# Schematic.net
KiCad netlist of a schematic drawn in Altium Designer
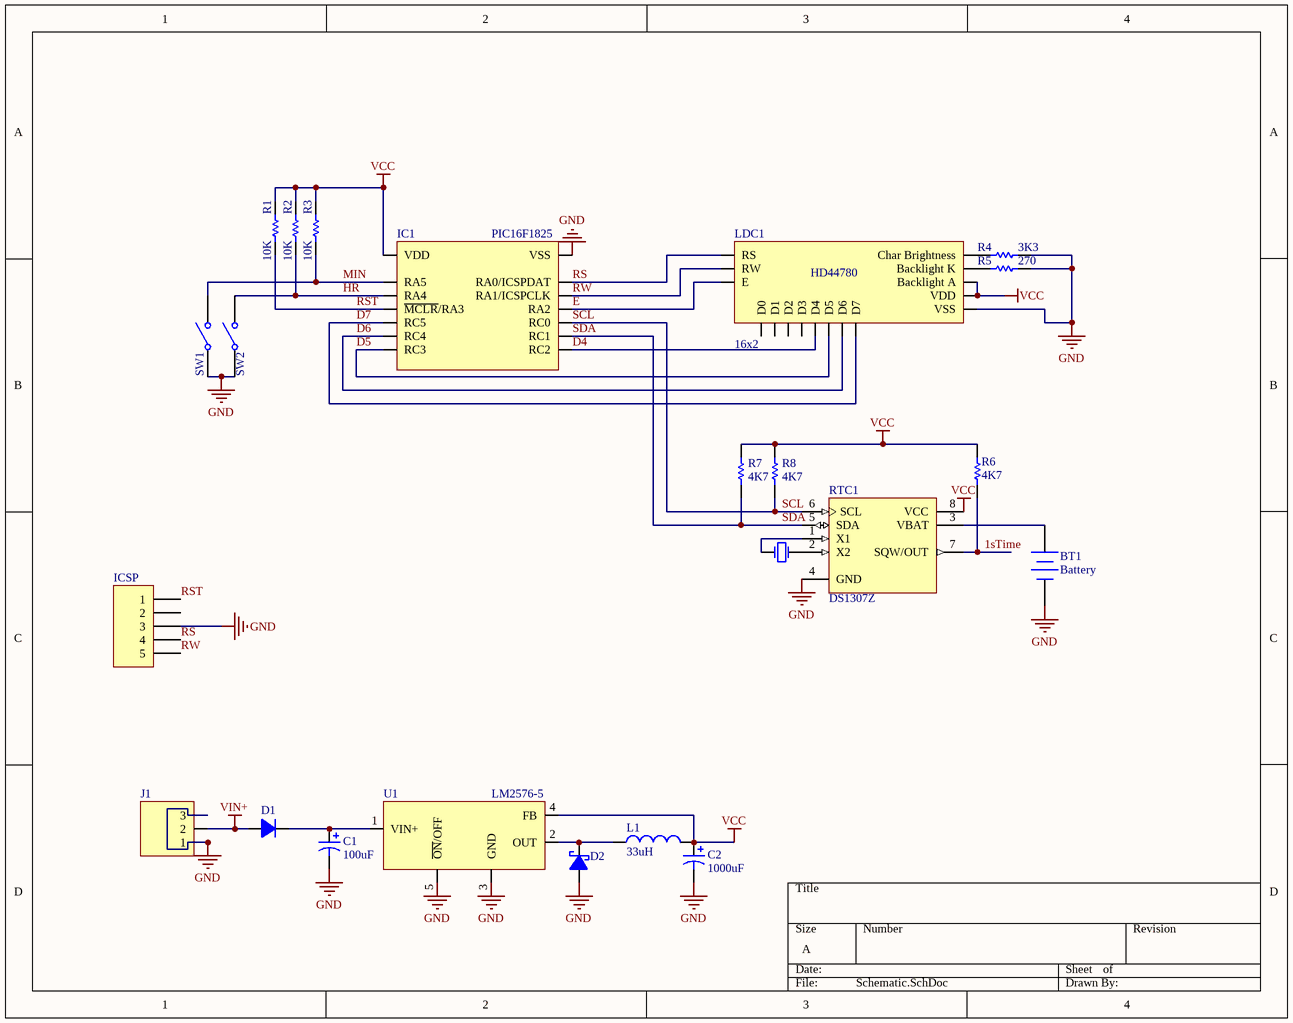
[diagram p0: Schematic.SchDoc]

(export (version "E")
  (design (tool "Eeschema 10.0.6"))
  (components
    (comp (ref "BT1")
      (value "Battery")
      (footprint "Moji Footprintovi:CR2032 Holder")
      (description "Multicell Battery")
      (fields (field (name "PUBLISHER") "Altium Limited"))
      (libsource (lib "Moji Schematici") (part "Battery"))
    )
    (comp (ref "C1")
      (value "100uF")
      (footprint "Electrolytic Cap2")
      (description "Polarized Capacitor (Axial)")
      (fields (field (name "Comment") "100uF / 50V") (field (name "PUBLISHER") "Altium Limited"))
      (libsource (lib "Moji Schematici") (part "Cap Electrolytic"))
    )
    (comp (ref "C2")
      (value "1000uF")
      (footprint "Electrolytic Cap2")
      (description "Polarized Capacitor (Axial)")
      (fields (field (name "Comment") "1000uF / 16V") (field (name "PUBLISHER") "Altium Limited"))
      (libsource (lib "Moji Schematici") (part "Cap Electrolytic"))
    )
    (comp (ref "D1")
      (value "Diode")
      (footprint "Moji Footprintovi:Axial 0.3 - Polarized")
      (fields (field (name "PUBLISHER") "Altium Limited"))
      (libsource (lib "Moji Schematici") (part "Diode"))
    )
    (comp (ref "D2")
      (value "1N5822")
      (footprint "Moji Footprintovi:Axial 0.3 - Polarized")
      (fields (field (name "PUBLISHER") "Altium Limited"))
      (libsource (lib "Moji Schematici") (part "Diode Schotky"))
    )
    (comp (ref "IC1")
      (value "PIC16F1825")
      (footprint "Moji Footprintovi:DIP14-300mil")
      (libsource (lib "Moji Schematici") (part "PIC16F1825"))
    )
    (comp (ref "ICSP")
      (value "Header 5")
      (footprint "HDR1X5")
      (description "Header, 5-Pin")
      (fields (field (name "PUBLISHER") "Altium Limited"))
      (libsource (lib "Miscellaneous Connectors") (part "Header 5"))
    )
    (comp (ref "J1")
      (value "Jack Mini Inline")
      (footprint "Jack Mini Inline")
      (libsource (lib "Moji Schematici") (part "Jack Mini Inline"))
    )
    (comp (ref "L1")
      (value "33uH")
      (footprint "Moji Footprintovi:CW8A")
      (description "Inductor")
      (fields (field (name "PUBLISHER") "Altium Limited"))
      (libsource (lib "Moji Schematici") (part "Inductor"))
    )
    (comp (ref "LDC1")
      (value "16x2")
      (footprint "Moji Footprintovi:HD44780")
      (description "HD44780 16x2 LCD Display")
      (libsource (lib "Moji Schematici") (part "HD44780"))
    )
    (comp (ref "R1")
      (value "10K")
      (footprint "Moji Footprintovi:0805")
      (description "Resistor")
      (fields (field (name "Comment") "Res") (field (name "PUBLISHER") "Altium Limited"))
      (libsource (lib "Moji Schematici") (part "Res"))
    )
    (comp (ref "R2")
      (value "10K")
      (footprint "Moji Footprintovi:0805")
      (description "Resistor")
      (fields (field (name "Comment") "Res") (field (name "PUBLISHER") "Altium Limited"))
      (libsource (lib "Moji Schematici") (part "Res"))
    )
    (comp (ref "R3")
      (value "10K")
      (footprint "Moji Footprintovi:0805")
      (description "Resistor")
      (fields (field (name "Comment") "Res") (field (name "PUBLISHER") "Altium Limited"))
      (libsource (lib "Moji Schematici") (part "Res"))
    )
    (comp (ref "R4")
      (value "3K3")
      (footprint "Moji Footprintovi:Axial 0.4")
      (description "Resistor")
      (fields (field (name "Comment") "Res") (field (name "PUBLISHER") "Altium Limited"))
      (libsource (lib "Moji Schematici") (part "Res"))
    )
    (comp (ref "R5")
      (value "270")
      (footprint "Moji Footprintovi:Axial 0.4")
      (description "Resistor")
      (fields (field (name "Comment") "Res") (field (name "PUBLISHER") "Altium Limited"))
      (libsource (lib "Moji Schematici") (part "Res"))
    )
    (comp (ref "R6")
      (value "4K7")
      (footprint "Moji Footprintovi:0805")
      (description "Resistor")
      (fields (field (name "Comment") "Res") (field (name "PUBLISHER") "Altium Limited"))
      (libsource (lib "Moji Schematici") (part "Res"))
    )
    (comp (ref "R7")
      (value "4K7")
      (footprint "Moji Footprintovi:0805")
      (description "Resistor")
      (fields (field (name "Comment") "Res") (field (name "PUBLISHER") "Altium Limited"))
      (libsource (lib "Moji Schematici") (part "Res"))
    )
    (comp (ref "R8")
      (value "4K7")
      (footprint "Moji Footprintovi:0805")
      (description "Resistor")
      (fields (field (name "Comment") "Res") (field (name "PUBLISHER") "Altium Limited"))
      (libsource (lib "Moji Schematici") (part "Res"))
    )
    (comp (ref "RTC1")
      (value "DS1307Z")
      (footprint "SOIC8N_N")
      (description "64 X 8 Serial Real-Time Clock")
      (fields (field (name "PUBLISHER") "Altium Limited"))
      (libsource (lib "Dallas Peripheral Real Time Clock") (part "DS1307Z"))
    )
    (comp (ref "SW1")
      (value "Switch")
      (footprint "SMD Switch 2pin")
      (libsource (lib "Moji Schematici") (part "Switch"))
    )
    (comp (ref "SW2")
      (value "Switch")
      (footprint "SMD Switch 2pin")
      (libsource (lib "Moji Schematici") (part "Switch"))
    )
    (comp (ref "U1")
      (value "LM2576-5")
      (footprint "Moji Footprintovi:TO263-5")
      (libsource (lib "Moji Schematici") (part "LM257-xx"))
    )
    (comp (ref "Y1")
      (value "XTAL")
      (footprint "Moji Footprintovi:XTAL-Watch")
      (description "Crystal Oscillator")
      (fields (field (name "PUBLISHER") "Altium Limited"))
      (libsource (lib "Moji Schematici") (part "XTAL"))
    )
  )
  (nets
    (net (code "1") (name "/1sTime") (class "Default")
      (node (ref "R6") (pin "2") (pinfunction "2_2") (pintype "passive"))
      (node (ref "RTC1") (pin "7") (pinfunction "SQW/OUT_7") (pintype "output"))
    )
    (net (code "2") (name "/D4") (class "Default")
      (node (ref "IC1") (pin "8") (pinfunction "RC2_8") (pintype "passive"))
      (node (ref "LDC1") (pin "D4") (pinfunction "D4_D4") (pintype "passive"))
    )
    (net (code "3") (name "/D5") (class "Default")
      (node (ref "IC1") (pin "7") (pinfunction "RC3_7") (pintype "passive"))
      (node (ref "LDC1") (pin "D5") (pinfunction "D5_D5") (pintype "passive"))
    )
    (net (code "4") (name "/D6") (class "Default")
      (node (ref "IC1") (pin "6") (pinfunction "RC4_6") (pintype "passive"))
      (node (ref "LDC1") (pin "D6") (pinfunction "D6_D6") (pintype "passive"))
    )
    (net (code "5") (name "/D7") (class "Default")
      (node (ref "IC1") (pin "5") (pinfunction "RC5_5") (pintype "passive"))
      (node (ref "LDC1") (pin "D7") (pinfunction "D7_D7") (pintype "passive"))
    )
    (net (code "6") (name "/E") (class "Default")
      (node (ref "IC1") (pin "11") (pinfunction "RA2_11") (pintype "passive"))
      (node (ref "LDC1") (pin "E") (pinfunction "E_E") (pintype "passive"))
    )
    (net (code "7") (name "/HR") (class "Default")
      (node (ref "IC1") (pin "3") (pinfunction "RA4_3") (pintype "passive"))
      (node (ref "R2") (pin "1") (pinfunction "1_1") (pintype "passive"))
      (node (ref "SW2") (pin "2") (pinfunction "COMMON2_2") (pintype "passive"))
    )
    (net (code "8") (name "/MIN") (class "Default")
      (node (ref "IC1") (pin "2") (pinfunction "RA5_2") (pintype "passive"))
      (node (ref "R3") (pin "1") (pinfunction "1_1") (pintype "passive"))
      (node (ref "SW1") (pin "2") (pinfunction "COMMON2_2") (pintype "passive"))
    )
    (net (code "9") (name "/RS") (class "Default")
      (node (ref "IC1") (pin "13") (pinfunction "RA0/ICSPDAT_13") (pintype "passive"))
      (node (ref "ICSP") (pin "4") (pinfunction "4_4") (pintype "passive"))
      (node (ref "LDC1") (pin "RS") (pinfunction "RS_RS") (pintype "passive"))
    )
    (net (code "10") (name "/RST") (class "Default")
      (node (ref "IC1") (pin "4") (pinfunction "~{MCLR}/RA3_4") (pintype "passive"))
      (node (ref "ICSP") (pin "1") (pinfunction "1_1") (pintype "passive"))
      (node (ref "R1") (pin "1") (pinfunction "1_1") (pintype "passive"))
    )
    (net (code "11") (name "/RW") (class "Default")
      (node (ref "IC1") (pin "12") (pinfunction "RA1/ICSPCLK_12") (pintype "passive"))
      (node (ref "ICSP") (pin "5") (pinfunction "5_5") (pintype "passive"))
      (node (ref "LDC1") (pin "RW") (pinfunction "RW_RW") (pintype "passive"))
    )
    (net (code "12") (name "/SCL") (class "Default")
      (node (ref "IC1") (pin "10") (pinfunction "RC0_10") (pintype "passive"))
      (node (ref "R8") (pin "1") (pinfunction "1_1") (pintype "passive"))
      (node (ref "RTC1") (pin "6") (pinfunction "SCL_6") (pintype "input"))
    )
    (net (code "13") (name "/SDA") (class "Default")
      (node (ref "IC1") (pin "9") (pinfunction "RC1_9") (pintype "passive"))
      (node (ref "R7") (pin "1") (pinfunction "1_1") (pintype "passive"))
      (node (ref "RTC1") (pin "5") (pinfunction "SDA_5") (pintype "bidirectional"))
    )
    (net (code "14") (name "GND") (class "Default")
      (node (ref "BT1") (pin "2") (pinfunction "-_2") (pintype "passive"))
      (node (ref "C1") (pin "2") (pinfunction "2_2") (pintype "passive"))
      (node (ref "C2") (pin "2") (pinfunction "2_2") (pintype "passive"))
      (node (ref "D2") (pin "A") (pinfunction "A_A") (pintype "passive"))
      (node (ref "IC1") (pin "14") (pinfunction "VSS_14") (pintype "passive"))
      (node (ref "ICSP") (pin "3") (pinfunction "3_3") (pintype "passive"))
      (node (ref "J1") (pin "1") (pinfunction "1_1") (pintype "passive"))
      (node (ref "J1") (pin "3") (pinfunction "3_3") (pintype "passive"))
      (node (ref "LDC1") (pin "VSS") (pinfunction "VSS_VSS") (pintype "passive"))
      (node (ref "R4") (pin "2") (pinfunction "2_2") (pintype "passive"))
      (node (ref "R5") (pin "1") (pinfunction "1_1") (pintype "passive"))
      (node (ref "RTC1") (pin "4") (pinfunction "GND_4") (pintype "power_in"))
      (node (ref "SW1") (pin "1") (pinfunction "COMMON1_1") (pintype "passive"))
      (node (ref "SW2") (pin "1") (pinfunction "COMMON1_1") (pintype "passive"))
      (node (ref "U1") (pin "3") (pinfunction "GND_3") (pintype "passive"))
      (node (ref "U1") (pin "5") (pinfunction "~{ON}/OFF_5") (pintype "passive"))
    )
    (net (code "15") (name "Net-(BT1-+)") (class "Default")
      (node (ref "BT1") (pin "1") (pinfunction "+_1") (pintype "passive"))
      (node (ref "RTC1") (pin "3") (pinfunction "VBAT_3") (pintype "power_in"))
    )
    (net (code "16") (name "Net-(LDC1-Backlight_K)") (class "Default")
      (node (ref "LDC1") (pin "K") (pinfunction "Backlight_K_K") (pintype "passive"))
      (node (ref "R5") (pin "2") (pinfunction "2_2") (pintype "passive"))
    )
    (net (code "17") (name "Net-(LDC1-Char_Brightness)") (class "Default")
      (node (ref "LDC1") (pin "BRTN") (pinfunction "Char_Brightness_BRTN") (pintype "passive"))
      (node (ref "R4") (pin "1") (pinfunction "1_1") (pintype "passive"))
    )
    (net (code "18") (name "Net-(RTC1-X1)") (class "Default")
      (node (ref "RTC1") (pin "1") (pinfunction "X1_1") (pintype "input"))
      (node (ref "Y1") (pin "1") (pinfunction "OSC1_1") (pintype "passive"))
    )
    (net (code "19") (name "Net-(RTC1-X2)") (class "Default")
      (node (ref "RTC1") (pin "2") (pinfunction "X2_2") (pintype "input"))
      (node (ref "Y1") (pin "2") (pinfunction "OSC2_2") (pintype "passive"))
    )
    (net (code "20") (name "Net-(U1-OUT)") (class "Default")
      (node (ref "D2") (pin "K") (pinfunction "K_K") (pintype "passive"))
      (node (ref "L1") (pin "1") (pinfunction "1_1") (pintype "passive"))
      (node (ref "U1") (pin "2") (pinfunction "OUT_2") (pintype "passive"))
    )
    (net (code "21") (name "Net-(U1-VIN+)") (class "Default")
      (node (ref "C1") (pin "1") (pinfunction "1_1") (pintype "passive"))
      (node (ref "D1") (pin "K") (pinfunction "K_K") (pintype "passive"))
      (node (ref "U1") (pin "1") (pinfunction "VIN+_1") (pintype "passive"))
    )
    (net (code "22") (name "VCC") (class "Default")
      (node (ref "C2") (pin "1") (pinfunction "1_1") (pintype "passive"))
      (node (ref "IC1") (pin "1") (pinfunction "VDD_1") (pintype "passive"))
      (node (ref "L1") (pin "2") (pinfunction "2_2") (pintype "passive"))
      (node (ref "LDC1") (pin "A") (pinfunction "Backlight_A_A") (pintype "passive"))
      (node (ref "LDC1") (pin "VDD") (pinfunction "VDD_VDD") (pintype "passive"))
      (node (ref "R1") (pin "2") (pinfunction "2_2") (pintype "passive"))
      (node (ref "R2") (pin "2") (pinfunction "2_2") (pintype "passive"))
      (node (ref "R3") (pin "2") (pinfunction "2_2") (pintype "passive"))
      (node (ref "R6") (pin "1") (pinfunction "1_1") (pintype "passive"))
      (node (ref "R7") (pin "2") (pinfunction "2_2") (pintype "passive"))
      (node (ref "R8") (pin "2") (pinfunction "2_2") (pintype "passive"))
      (node (ref "RTC1") (pin "8") (pinfunction "VCC_8") (pintype "power_in"))
      (node (ref "U1") (pin "4") (pinfunction "FB_4") (pintype "passive"))
    )
    (net (code "23") (name "VIN+") (class "Default")
      (node (ref "D1") (pin "A") (pinfunction "A_A") (pintype "passive"))
      (node (ref "J1") (pin "2") (pinfunction "2_2") (pintype "passive"))
    )
    (net (code "24") (name "unconnected-(ICSP-Pad2)") (class "Default")
      (node (ref "ICSP") (pin "2") (pinfunction "2_2") (pintype "passive"))
    )
    (net (code "25") (name "unconnected-(LDC1-PadD0)") (class "Default")
      (node (ref "LDC1") (pin "D0") (pinfunction "D0_D0") (pintype "passive"))
    )
    (net (code "26") (name "unconnected-(LDC1-PadD1)") (class "Default")
      (node (ref "LDC1") (pin "D1") (pinfunction "D1_D1") (pintype "passive"))
    )
    (net (code "27") (name "unconnected-(LDC1-PadD2)") (class "Default")
      (node (ref "LDC1") (pin "D2") (pinfunction "D2_D2") (pintype "passive"))
    )
    (net (code "28") (name "unconnected-(LDC1-PadD3)") (class "Default")
      (node (ref "LDC1") (pin "D3") (pinfunction "D3_D3") (pintype "passive"))
    )
  )
)
